# DMP_SEM_POWER.net
KiCad netlist of a schematic drawn in Altium Designer
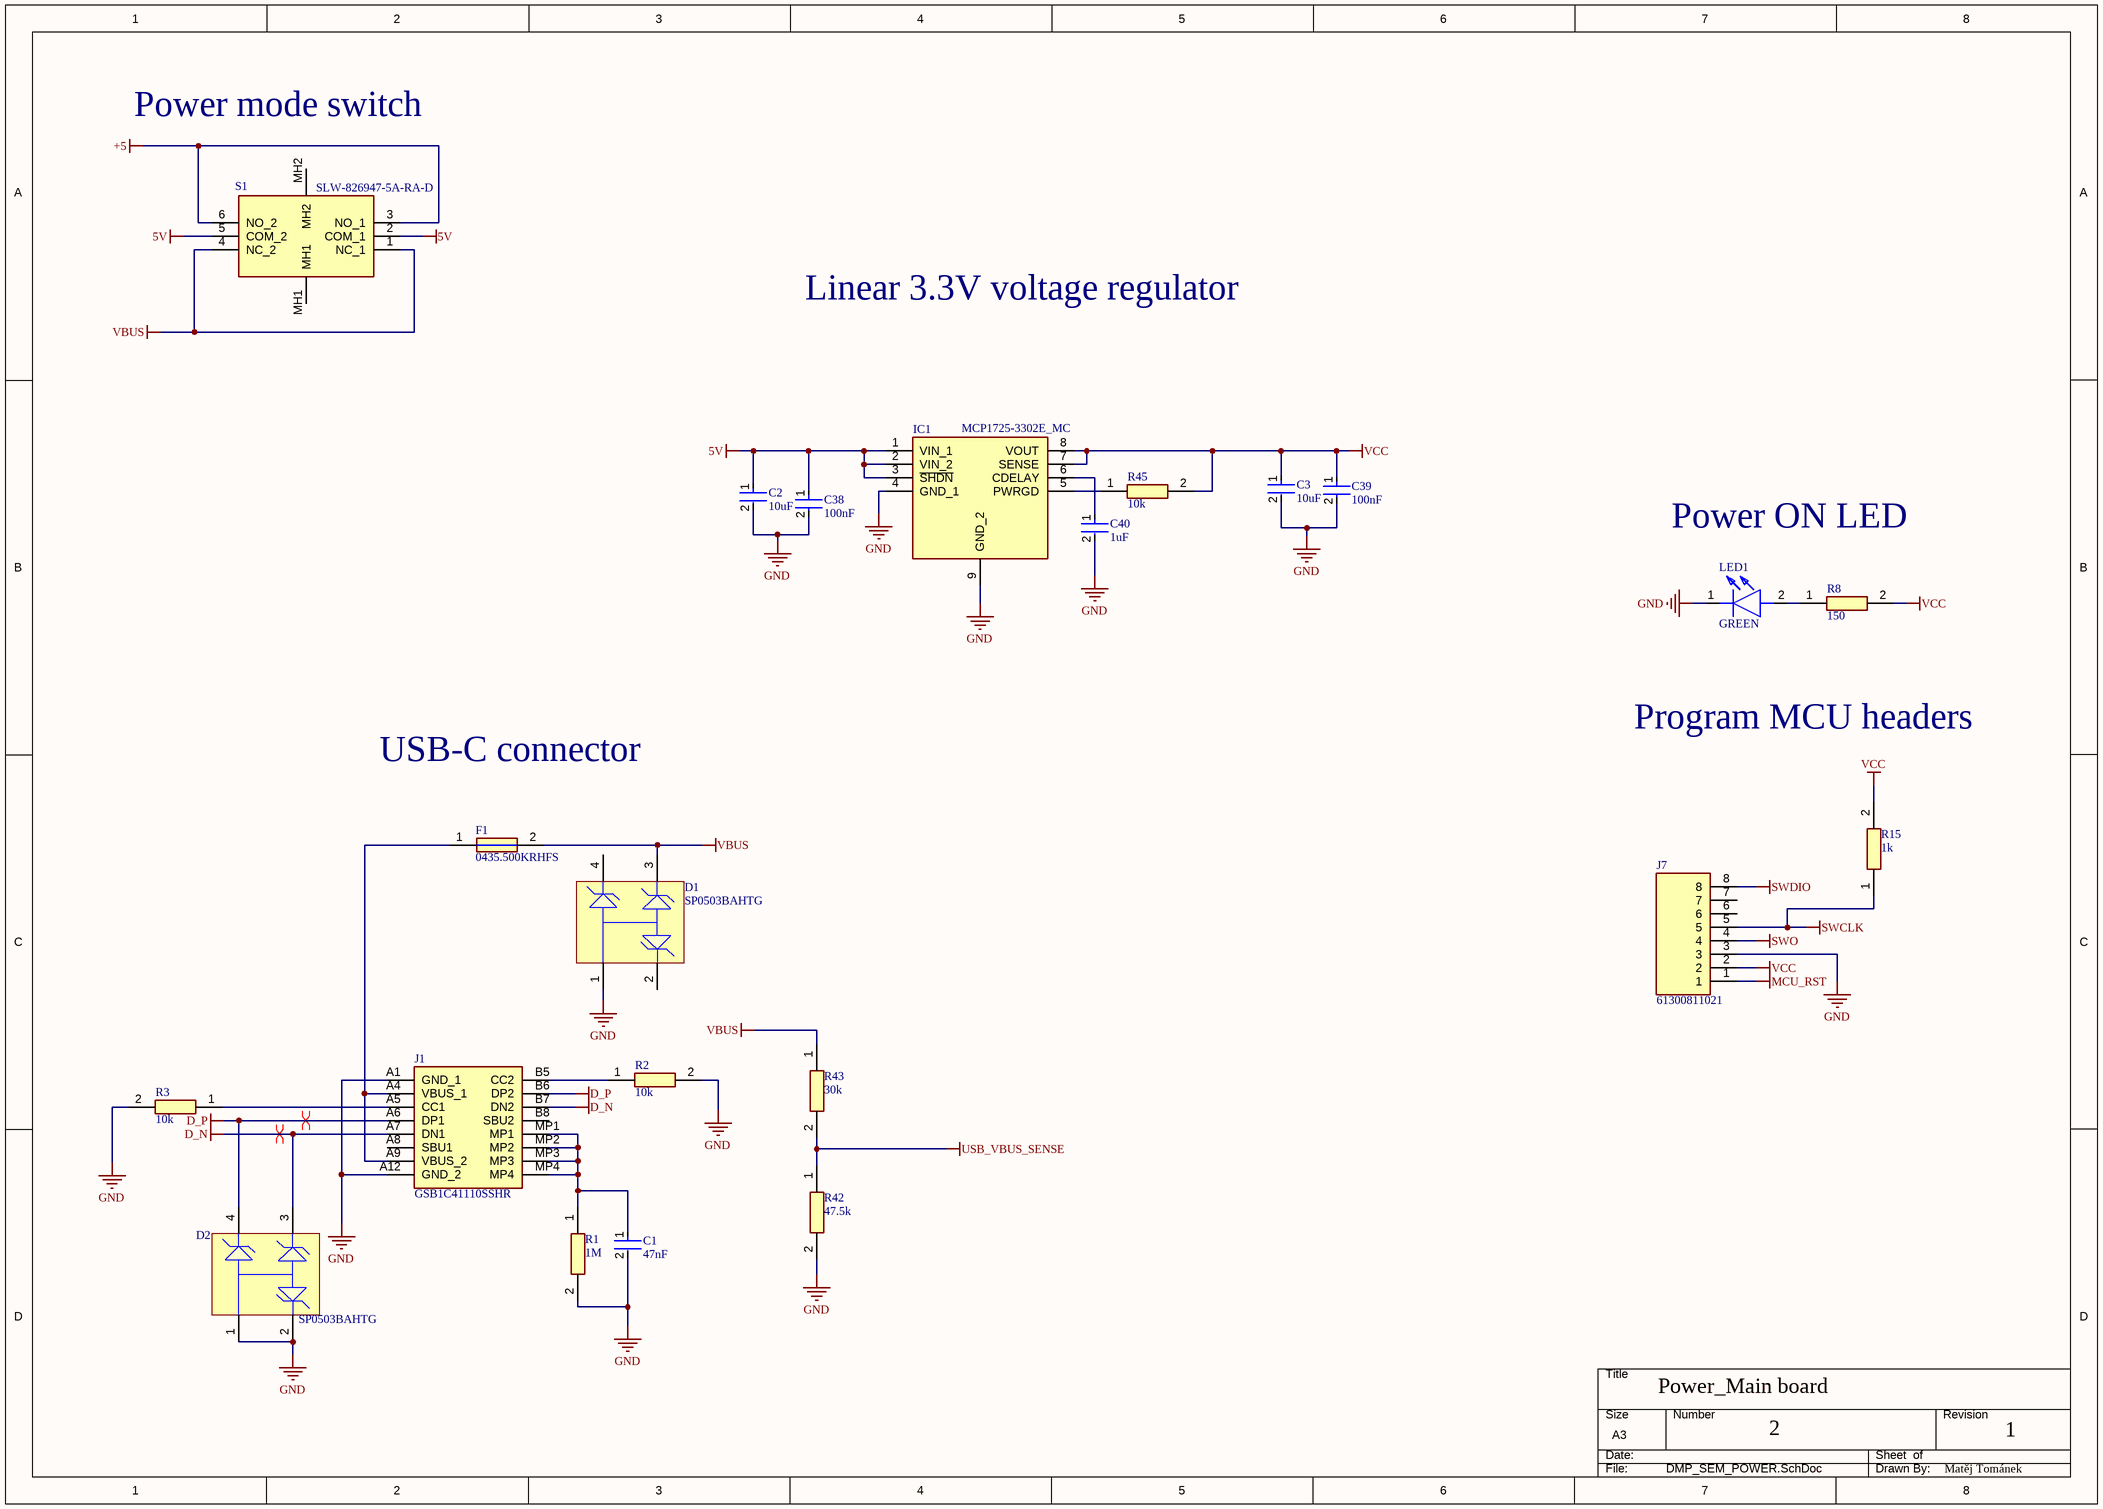
[diagram p0: DMP_SEM_POWER.SchDoc]

(export (version "E")
  (design (tool "Eeschema 10.0.6"))
  (components
    (comp (ref "C1")
      (value "47nF")
      (footprint "C0603X473J3RAC3316")
      (description "Capacitor C0603X473J3RAC3316")
      (libsource (lib "DMP_Schlib_SEM_MAIN_BOARD") (part "C0603X473J3RAC3316"))
    )
    (comp (ref "C2")
      (value "10uF")
      (footprint "CL10A106KO8NQNC")
      (description "Capacitor CL10A106KO8NQNC")
      (libsource (lib "DMP_Schlib_SEM_MAIN_BOARD") (part "CL10A106KO8NQNC"))
    )
    (comp (ref "C3")
      (value "10uF")
      (footprint "CL10A106KO8NQNC")
      (description "Capacitor CL10A106KO8NQNC")
      (libsource (lib "DMP_Schlib_SEM_MAIN_BOARD") (part "CL10A106KO8NQNC"))
    )
    (comp (ref "C38")
      (value "100nF")
      (footprint "CL05B104KO5NNNC")
      (description "Capacitor CL05B104KO5NNNC")
      (libsource (lib "DMP_Schlib_SEM_MAIN_BOARD") (part "CL05B104KO5NNNC"))
    )
    (comp (ref "C39")
      (value "100nF")
      (footprint "CL05B104KO5NNNC")
      (description "Capacitor CL05B104KO5NNNC")
      (libsource (lib "DMP_Schlib_SEM_MAIN_BOARD") (part "CL05B104KO5NNNC"))
    )
    (comp (ref "C40")
      (value "1uF")
      (footprint "GRM155C81C105KE11D")
      (description "Capacitor GRM155C81C105KE11D")
      (libsource (lib "DMP_Schlib_SEM_MAIN_BOARD") (part "GRM155C81C105KE11D"))
    )
    (comp (ref "D1")
      (value "SP0503BAHTG")
      (footprint "SP0503BAHTG")
      (description "TVS Diodes SP0503BAHTG")
      (libsource (lib "DMP_Schlib_SEM_MAIN_BOARD") (part "SP0503BAHTG"))
    )
    (comp (ref "D2")
      (value "SP0503BAHTG")
      (footprint "SP0503BAHTG")
      (description "TVS Diodes SP0503BAHTG")
      (libsource (lib "DMP_Schlib_SEM_MAIN_BOARD") (part "SP0503BAHTG"))
    )
    (comp (ref "F1")
      (value "0435.500KRHFS")
      (footprint "0435.500KRHFS")
      (description "Fuse 0435.500KRHFS")
      (libsource (lib "DMP_Schlib_SEM_MAIN_BOARD") (part "0435.500KRHFS"))
    )
    (comp (ref "IC1")
      (value "MCP1725-3302E_MC")
      (footprint "MCP1725-3302E_MC")
      (description "Linear voltage regulator  MCP1725-3302E_MC")
      (libsource (lib "DMP_Schlib_SEM_MAIN_BOARD") (part "MCP1725-3302E_MC"))
    )
    (comp (ref "J1")
      (value "GSB1C41110SSHR")
      (footprint "GSB1C41110SSHR")
      (description "USB-C Connector")
      (libsource (lib "DMP_Schlib_SEM_MAIN_BOARD") (part "GSB1C41110SSHR"))
    )
    (comp (ref "J7")
      (value "61300811021")
      (footprint "61300811021")
      (description "Programing connector 61300811021")
      (libsource (lib "DMP_Schlib_SEM_MAIN_BOARD") (part "61300811021"))
    )
    (comp (ref "LED1")
      (value "GREEN")
      (footprint "SMLEN3EC8TT86")
      (description "GREEN LED Diode")
      (libsource (lib "DMP_Schlib_SEM_MAIN_BOARD") (part "SMLEN3EC8TT86"))
    )
    (comp (ref "R1")
      (value "1M")
      (footprint "RC0402FR-071ML")
      (description "Resistor RC0402FR-071ML")
      (libsource (lib "DMP_Schlib_SEM_MAIN_BOARD") (part "RC0402FR-071ML"))
    )
    (comp (ref "R2")
      (value "10k")
      (footprint "CRCW060310K0FKEA")
      (description "Resistor CRCW060310K0FKEA")
      (libsource (lib "") (part "CRCW060310K0FKEA_1"))
    )
    (comp (ref "R3")
      (value "10k")
      (footprint "CRCW060310K0FKEA")
      (description "Resistor CRCW060310K0FKEA")
      (libsource (lib "DMP_Schlib_SEM_MAIN_BOARD") (part "CRCW060310K0FKEA"))
    )
    (comp (ref "R8")
      (value "150")
      (footprint "CRCW0402150RFKEDHP")
      (description "Resistor CRCW0402150RFKEDHP")
      (libsource (lib "DMP_Schlib_SEM_MAIN_BOARD") (part "CRCW0402150RFKEDHP"))
    )
    (comp (ref "R15")
      (value "1k")
      (footprint "RC0603FR-071KL")
      (description "Resistor RC0603FR-071KL")
      (libsource (lib "DMP_Schlib_SEM_MAIN_BOARD") (part "RC0603FR-071KL"))
    )
    (comp (ref "R42")
      (value "47.5k")
      (footprint "ERJ-PA3D4752V")
      (description "Resistor ERJ-PA3D4752V")
      (libsource (lib "DMP_Schlib_SEM_MAIN_BOARD") (part "ERJ-PA3D4752V"))
    )
    (comp (ref "R43")
      (value "30k")
      (footprint "RT0603DRD0730KL")
      (description "Resistor RT0603DRD0730KL")
      (libsource (lib "DMP_Schlib_SEM_MAIN_BOARD") (part "RT0603DRD0730KL"))
    )
    (comp (ref "R45")
      (value "10k")
      (footprint "CRCW060310K0FKEA")
      (description "Resistor CRCW060310K0FKEA")
      (libsource (lib "") (part "CRCW060310K0FKEA_1"))
    )
    (comp (ref "S1")
      (value "SLW-826947-5A-RA-D")
      (footprint "SLW-826947-5A-RA-D")
      (description "Switch SLW-826947-5A-RA-D")
      (libsource (lib "DMP_Schlib_SEM_MAIN_BOARD") (part "SLW-826947-5A-RA-D"))
    )
  )
  (nets
    (net (code "1") (name "+5") (class "Default")
      (node (ref "S1") (pin "3") (pinfunction "NO_1_3") (pintype "passive"))
      (node (ref "S1") (pin "6") (pinfunction "NO_2_6") (pintype "passive"))
    )
    (net (code "2") (name "5V") (class "Default")
      (node (ref "C2") (pin "1") (pinfunction "1_1") (pintype "passive"))
      (node (ref "C38") (pin "1") (pinfunction "1_1") (pintype "passive"))
      (node (ref "IC1") (pin "1") (pinfunction "VIN_1_1") (pintype "passive"))
      (node (ref "IC1") (pin "2") (pinfunction "VIN_2_2") (pintype "passive"))
      (node (ref "IC1") (pin "3") (pinfunction "~{SHDN}_3") (pintype "passive"))
      (node (ref "S1") (pin "2") (pinfunction "COM_1_2") (pintype "passive"))
      (node (ref "S1") (pin "5") (pinfunction "COM_2_5") (pintype "passive"))
    )
    (net (code "3") (name "D_N") (class "Default")
      (node (ref "D2") (pin "3") (pinfunction "3_3") (pintype "passive"))
      (node (ref "J1") (pin "A7") (pinfunction "DN1_A7") (pintype "passive"))
      (node (ref "J1") (pin "B7") (pinfunction "DN2_B7") (pintype "passive"))
    )
    (net (code "4") (name "D_P") (class "Default")
      (node (ref "D2") (pin "4") (pinfunction "4_4") (pintype "passive"))
      (node (ref "J1") (pin "A6") (pinfunction "DP1_A6") (pintype "passive"))
      (node (ref "J1") (pin "B6") (pinfunction "DP2_B6") (pintype "passive"))
    )
    (net (code "5") (name "GND") (class "Default")
      (node (ref "C1") (pin "2") (pinfunction "2_2") (pintype "passive"))
      (node (ref "C2") (pin "2") (pinfunction "2_2") (pintype "passive"))
      (node (ref "C3") (pin "2") (pinfunction "2_2") (pintype "passive"))
      (node (ref "C38") (pin "2") (pinfunction "2_2") (pintype "passive"))
      (node (ref "C39") (pin "2") (pinfunction "2_2") (pintype "passive"))
      (node (ref "C40") (pin "2") (pinfunction "2_2") (pintype "passive"))
      (node (ref "D1") (pin "1") (pinfunction "1_1") (pintype "passive"))
      (node (ref "D2") (pin "1") (pinfunction "1_1") (pintype "passive"))
      (node (ref "D2") (pin "2") (pinfunction "2_2") (pintype "passive"))
      (node (ref "IC1") (pin "4") (pinfunction "GND_1_4") (pintype "passive"))
      (node (ref "IC1") (pin "9") (pinfunction "GND_2_9") (pintype "passive"))
      (node (ref "J1") (pin "A1") (pinfunction "GND_1_A1") (pintype "passive"))
      (node (ref "J1") (pin "A12") (pinfunction "GND_2_A12") (pintype "passive"))
      (node (ref "J7") (pin "3") (pinfunction "3_3") (pintype "passive"))
      (node (ref "LED1") (pin "1") (pinfunction "K_1") (pintype "passive"))
      (node (ref "R1") (pin "2") (pinfunction "2_2") (pintype "passive"))
      (node (ref "R2") (pin "2") (pinfunction "2_2") (pintype "passive"))
      (node (ref "R3") (pin "2") (pinfunction "2_2") (pintype "passive"))
      (node (ref "R42") (pin "2") (pinfunction "2_2") (pintype "passive"))
    )
    (net (code "6") (name "MCU_RST") (class "Default")
      (node (ref "J7") (pin "1") (pinfunction "1_1") (pintype "passive"))
    )
    (net (code "7") (name "Net-(C1-Pad1)") (class "Default")
      (node (ref "C1") (pin "1") (pinfunction "1_1") (pintype "passive"))
      (node (ref "J1") (pin "MP1") (pinfunction "MP1_MP1") (pintype "passive"))
      (node (ref "J1") (pin "MP2") (pinfunction "MP2_MP2") (pintype "passive"))
      (node (ref "J1") (pin "MP3") (pinfunction "MP3_MP3") (pintype "passive"))
      (node (ref "J1") (pin "MP4") (pinfunction "MP4_MP4") (pintype "passive"))
      (node (ref "R1") (pin "1") (pinfunction "1_1") (pintype "passive"))
    )
    (net (code "8") (name "Net-(IC1-CDELAY)") (class "Default")
      (node (ref "C40") (pin "1") (pinfunction "1_1") (pintype "passive"))
      (node (ref "IC1") (pin "6") (pinfunction "CDELAY_6") (pintype "passive"))
    )
    (net (code "9") (name "Net-(IC1-PWRGD)") (class "Default")
      (node (ref "IC1") (pin "5") (pinfunction "PWRGD_5") (pintype "passive"))
      (node (ref "R45") (pin "1") (pinfunction "1_1") (pintype "passive"))
    )
    (net (code "10") (name "Net-(J1-CC1)") (class "Default")
      (node (ref "J1") (pin "A5") (pinfunction "CC1_A5") (pintype "passive"))
      (node (ref "R3") (pin "1") (pinfunction "1_1") (pintype "passive"))
    )
    (net (code "11") (name "Net-(J1-CC2)") (class "Default")
      (node (ref "J1") (pin "B5") (pinfunction "CC2_B5") (pintype "passive"))
      (node (ref "R2") (pin "1") (pinfunction "1_1") (pintype "passive"))
    )
    (net (code "12") (name "Net-(J1-VBUS_1)") (class "Default")
      (node (ref "F1") (pin "1") (pinfunction "1_1") (pintype "passive"))
      (node (ref "J1") (pin "A4") (pinfunction "VBUS_1_A4") (pintype "passive"))
      (node (ref "J1") (pin "A9") (pinfunction "VBUS_2_A9") (pintype "passive"))
    )
    (net (code "13") (name "Net-(LED1-A)") (class "Default")
      (node (ref "LED1") (pin "2") (pinfunction "A_2") (pintype "passive"))
      (node (ref "R8") (pin "1") (pinfunction "1_1") (pintype "passive"))
    )
    (net (code "14") (name "SWCLK") (class "Default")
      (node (ref "J7") (pin "5") (pinfunction "5_5") (pintype "passive"))
      (node (ref "R15") (pin "1") (pinfunction "1_1") (pintype "passive"))
    )
    (net (code "15") (name "SWDIO") (class "Default")
      (node (ref "J7") (pin "8") (pinfunction "8_8") (pintype "passive"))
    )
    (net (code "16") (name "SWO") (class "Default")
      (node (ref "J7") (pin "4") (pinfunction "4_4") (pintype "passive"))
    )
    (net (code "17") (name "USB_VBUS_SENSE") (class "Default")
      (node (ref "R42") (pin "1") (pinfunction "1_1") (pintype "passive"))
      (node (ref "R43") (pin "2") (pinfunction "2_2") (pintype "passive"))
    )
    (net (code "18") (name "VBUS") (class "Default")
      (node (ref "D1") (pin "3") (pinfunction "3_3") (pintype "passive"))
      (node (ref "F1") (pin "2") (pinfunction "2_2") (pintype "passive"))
      (node (ref "R43") (pin "1") (pinfunction "1_1") (pintype "passive"))
      (node (ref "S1") (pin "1") (pinfunction "NC_1_1") (pintype "passive"))
      (node (ref "S1") (pin "4") (pinfunction "NC_2_4") (pintype "passive"))
    )
    (net (code "19") (name "VCC") (class "Default")
      (node (ref "C3") (pin "1") (pinfunction "1_1") (pintype "passive"))
      (node (ref "C39") (pin "1") (pinfunction "1_1") (pintype "passive"))
      (node (ref "IC1") (pin "7") (pinfunction "SENSE_7") (pintype "passive"))
      (node (ref "IC1") (pin "8") (pinfunction "VOUT_8") (pintype "passive"))
      (node (ref "J7") (pin "2") (pinfunction "2_2") (pintype "passive"))
      (node (ref "R15") (pin "2") (pinfunction "2_2") (pintype "passive"))
      (node (ref "R45") (pin "2") (pinfunction "2_2") (pintype "passive"))
      (node (ref "R8") (pin "2") (pinfunction "2_2") (pintype "passive"))
    )
    (net (code "20") (name "unconnected-(D1-Pad2)") (class "Default")
      (node (ref "D1") (pin "2") (pinfunction "2_2") (pintype "passive"))
    )
    (net (code "21") (name "unconnected-(D1-Pad4)") (class "Default")
      (node (ref "D1") (pin "4") (pinfunction "4_4") (pintype "passive"))
    )
    (net (code "22") (name "unconnected-(J1-SBU1-PadA8)") (class "Default")
      (node (ref "J1") (pin "A8") (pinfunction "SBU1_A8") (pintype "passive"))
    )
    (net (code "23") (name "unconnected-(J1-SBU2-PadB8)") (class "Default")
      (node (ref "J1") (pin "B8") (pinfunction "SBU2_B8") (pintype "passive"))
    )
    (net (code "24") (name "unconnected-(J7-Pad6)") (class "Default")
      (node (ref "J7") (pin "6") (pinfunction "6_6") (pintype "passive"))
    )
    (net (code "25") (name "unconnected-(J7-Pad7)") (class "Default")
      (node (ref "J7") (pin "7") (pinfunction "7_7") (pintype "passive"))
    )
    (net (code "26") (name "unconnected-(S1-PadMH1)") (class "Default")
      (node (ref "S1") (pin "MH1") (pinfunction "MH1_MH1") (pintype "passive"))
    )
    (net (code "27") (name "unconnected-(S1-PadMH2)") (class "Default")
      (node (ref "S1") (pin "MH2") (pinfunction "MH2_MH2") (pintype "passive"))
    )
  )
)
